# FPGA.net
KiCad netlist of a schematic drawn in Altium Designer
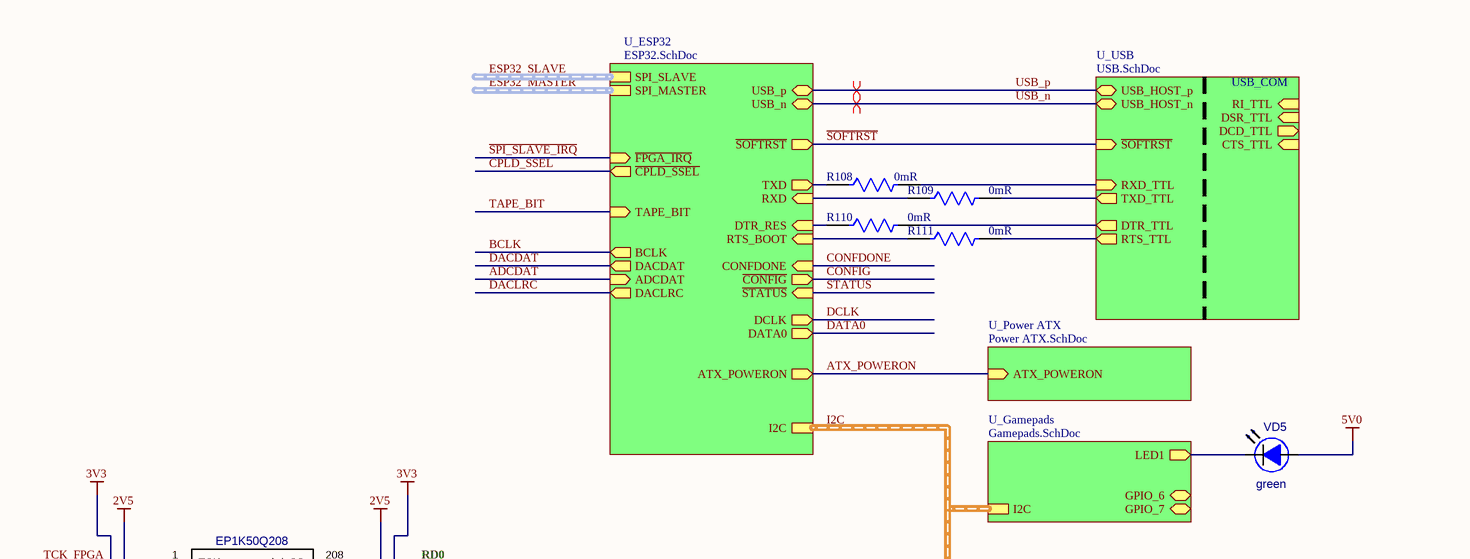
[diagram p0: FPGA.SchDoc, top]
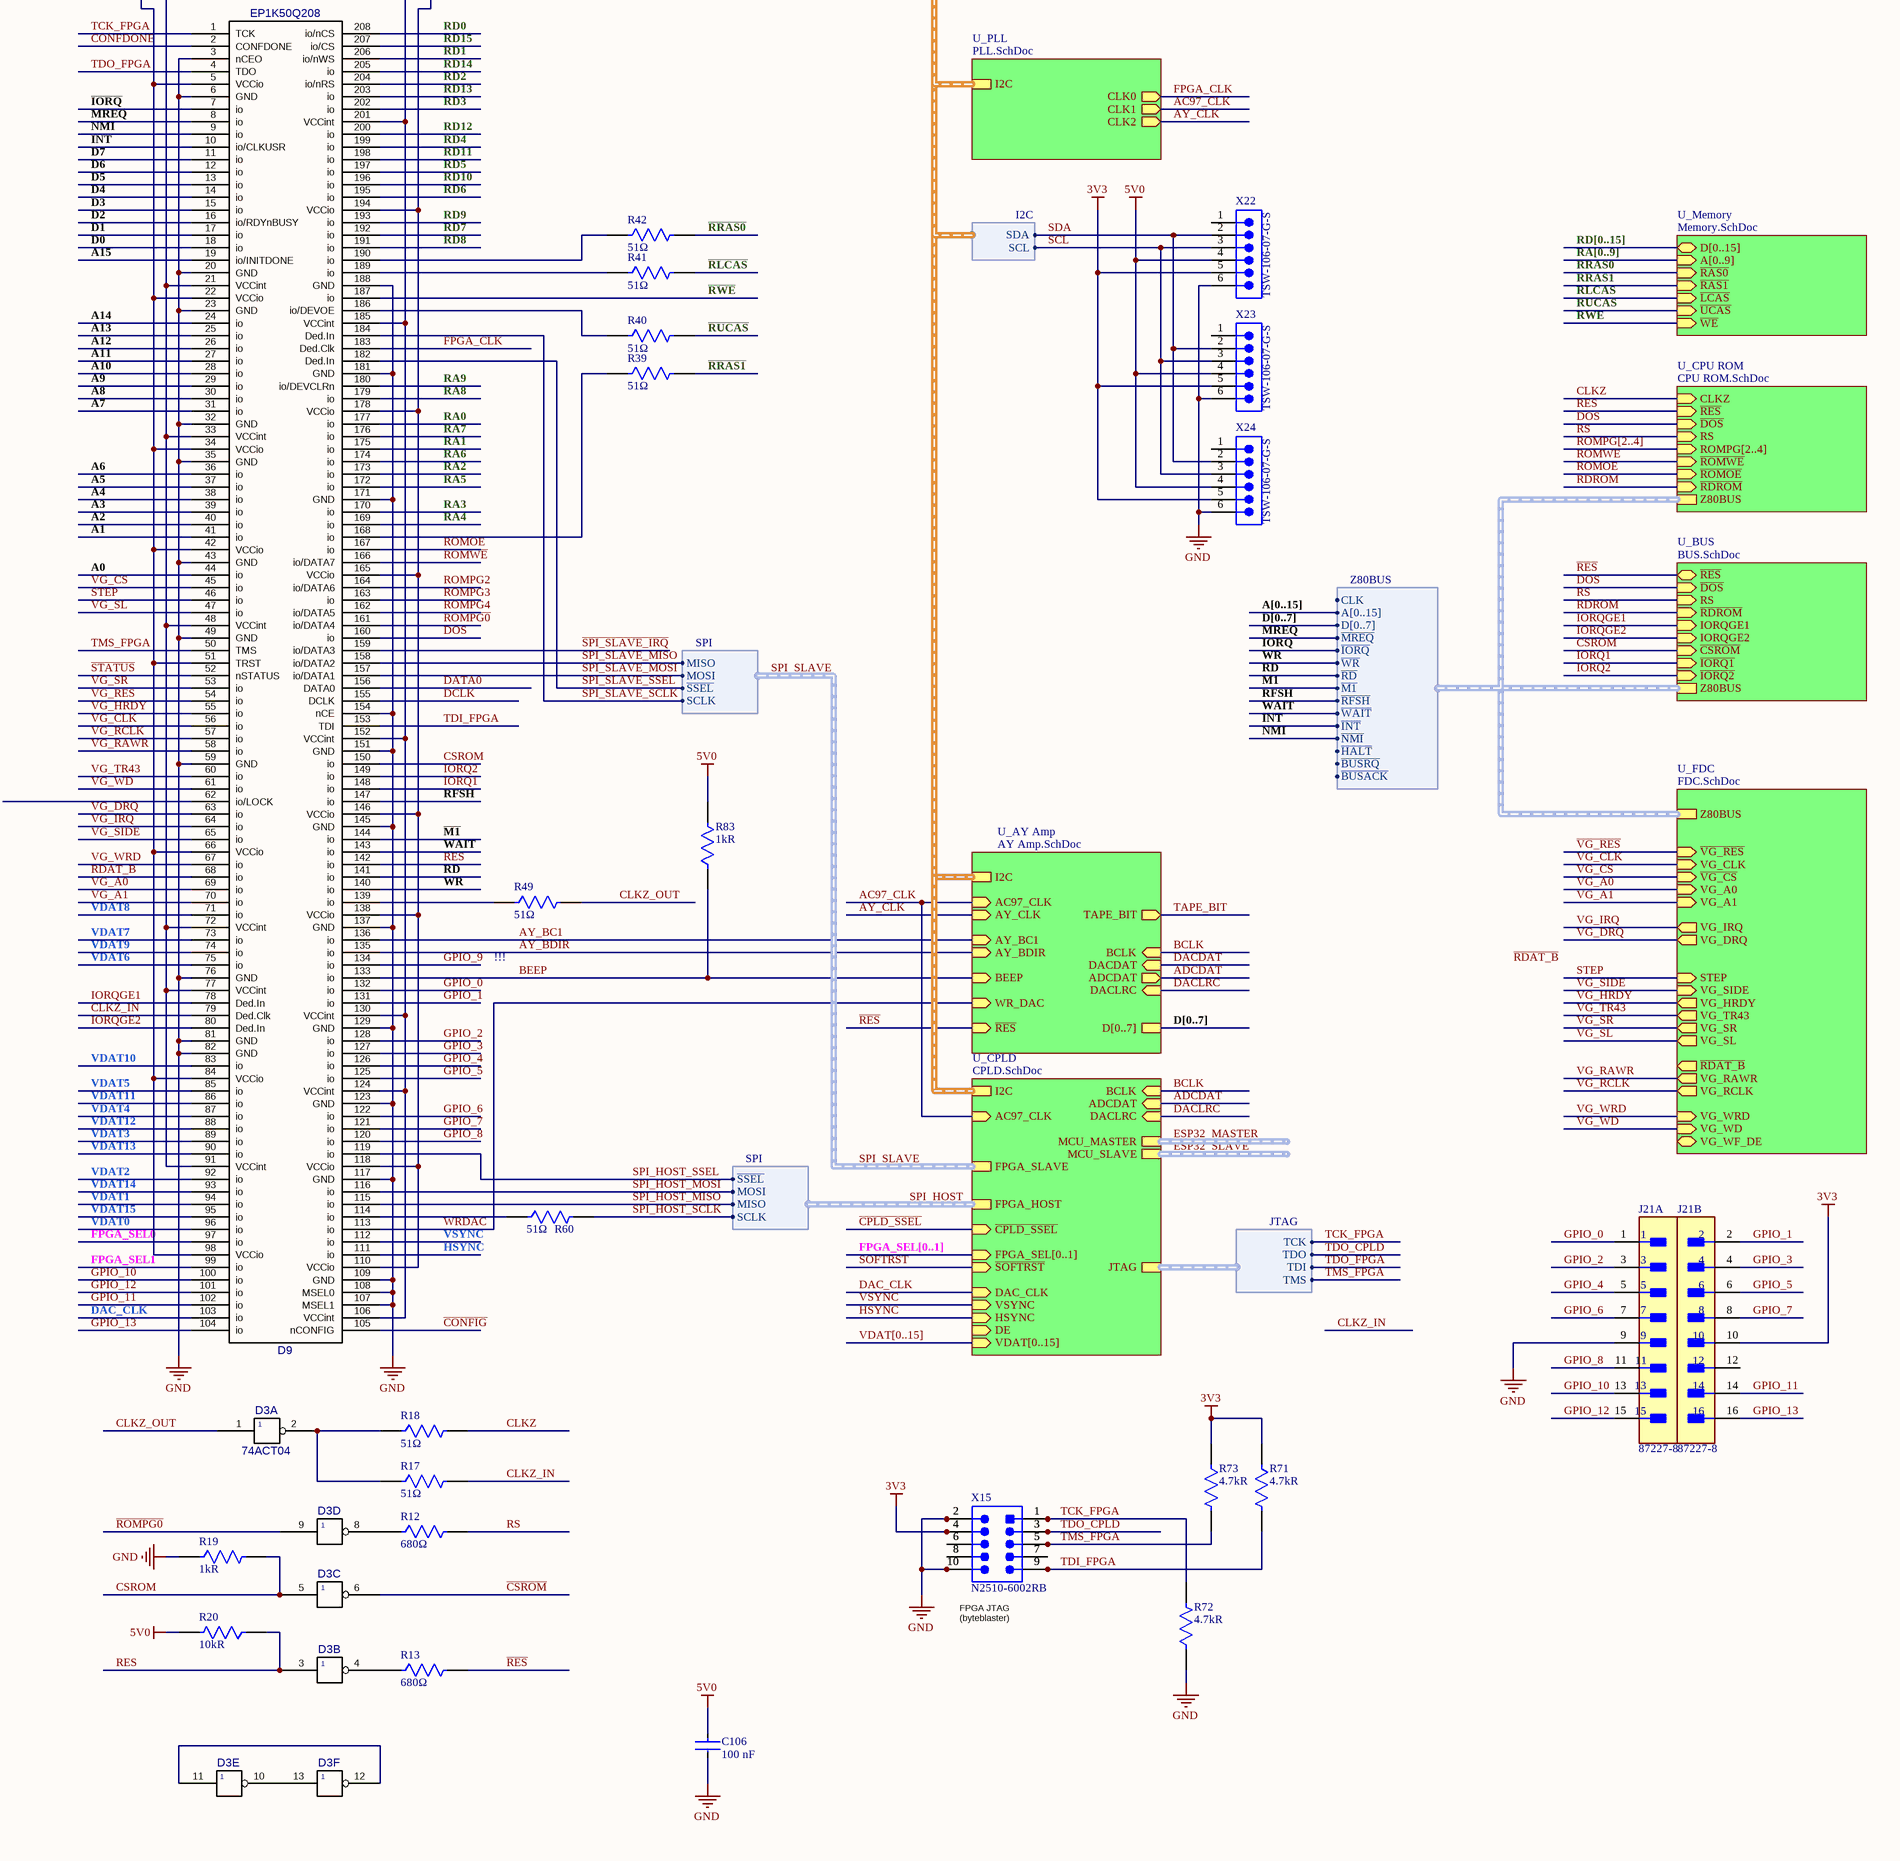
[diagram p1: FPGA.SchDoc, bottom]

(export (version "E")
  (design (tool "Eeschema 10.0.6"))
  (components
    (comp (ref "C106")
      (value "CC0805KRX7R9BB104")
      (footprint "FP-CC0805-0_85-IPC_A")
      (description "CAP CER 0.1UF 50V X7R 0805")
      (fields (field (name "CAPACITANCE") "100 nF") (field (name "MANUFACTURER") "Yageo"))
      (libsource (lib "SchLib") (part "CMP-2100-03606-3"))
    )
    (comp (ref "D3")
      (value "74ACT04")
      (footprint "SO14")
      (description "04")
      (libsource (lib "SchLib") (part "04"))
    )
    (comp (ref "D9")
      (value "EP1K50Q208")
      (footprint "PQFP208X5")
      (libsource (lib "SchLib") (part "EP1K50Q208"))
    )
    (comp (ref "J21")
      (value "87227-8")
      (footprint "FP-87227-8-MFG")
      (description "CONN HEADER VERT 16POS 2.54MM")
      (fields (field (name "MANUFACTURER") "TE Connectivity"))
      (libsource (lib "SchLib") (part "CMP-03369-000064-1"))
    )
    (comp (ref "R12")
      (value "680Ω")
      (footprint "FP-RT0805-IPC_A")
      (description "RES SMD 680 OHM 1% 1/8W 0805")
      (fields
        (field (name "MANUFACTURER") "Yageo")
        (field (name "MANUFACTURER PART NUMBER") "RT0805FRE07680RL")
      )
      (libsource (lib "SchLib") (part "CMP-03412-000082-1"))
    )
    (comp (ref "R13")
      (value "680Ω")
      (footprint "FP-RT0805-IPC_A")
      (description "RES SMD 680 OHM 1% 1/8W 0805")
      (fields
        (field (name "MANUFACTURER") "Yageo")
        (field (name "MANUFACTURER PART NUMBER") "RT0805FRE07680RL")
      )
      (libsource (lib "SchLib") (part "CMP-03412-000082-1"))
    )
    (comp (ref "R17")
      (value "RR1220Q-510-D")
      (footprint "FP-RR1220-IPC_A")
      (description "51Ω ±0.5% 0.1W 1/10W Chip Resistor 0805 (2012 Metric) Thin Film")
      (fields (field (name "RESISTANCE") "51Ω") (field (name "MANUFACTURER") "Susumu"))
      (libsource (lib "SchLib") (part "CMP-2001-03561-2"))
    )
    (comp (ref "R18")
      (value "RR1220Q-510-D")
      (footprint "FP-RR1220-IPC_A")
      (description "51Ω ±0.5% 0.1W 1/10W Chip Resistor 0805 (2012 Metric) Thin Film")
      (fields (field (name "RESISTANCE") "51Ω") (field (name "MANUFACTURER") "Susumu"))
      (libsource (lib "SchLib") (part "CMP-2001-03561-2"))
    )
    (comp (ref "R19")
      (value "CRCW08051K00FKEAHP")
      (footprint "FP-CRCW0805-HPe3-IPC_A")
      (description "RES Thick Film, 1kΩ, 1%, 0.5W, 100ppm/°C, 0805")
      (fields (field (name "RESISTANCE") "1kR") (field (name "MANUFACTURER") "Vishay Dale"))
      (libsource (lib "SchLib") (part "CMP-02407-004529-1"))
    )
    (comp (ref "R20")
      (value "CR0805-JW-103ELF")
      (footprint "FP-CR0805-IPC_A")
      (description "Thick Film Chip Resistors 0805 10kΩ 0.125W 5% 200ppm/°C")
      (fields (field (name "RESISTANCE") "10kR") (field (name "MANUFACTURER") "Bourns"))
      (libsource (lib "SchLib") (part "CMP-07231-003873-1"))
    )
    (comp (ref "R39")
      (value "RR1220Q-510-D")
      (footprint "FP-RR1220-IPC_A")
      (description "51Ω ±0.5% 0.1W 1/10W Chip Resistor 0805 (2012 Metric) Thin Film")
      (fields (field (name "RESISTANCE") "51Ω") (field (name "MANUFACTURER") "Susumu"))
      (libsource (lib "SchLib") (part "CMP-2001-03561-2"))
    )
    (comp (ref "R40")
      (value "RR1220Q-510-D")
      (footprint "FP-RR1220-IPC_A")
      (description "51Ω ±0.5% 0.1W 1/10W Chip Resistor 0805 (2012 Metric) Thin Film")
      (fields (field (name "RESISTANCE") "51Ω") (field (name "MANUFACTURER") "Susumu"))
      (libsource (lib "SchLib") (part "CMP-2001-03561-2"))
    )
    (comp (ref "R41")
      (value "RR1220Q-510-D")
      (footprint "FP-RR1220-IPC_A")
      (description "51Ω ±0.5% 0.1W 1/10W Chip Resistor 0805 (2012 Metric) Thin Film")
      (fields (field (name "RESISTANCE") "51Ω") (field (name "MANUFACTURER") "Susumu"))
      (libsource (lib "SchLib") (part "CMP-2001-03561-2"))
    )
    (comp (ref "R42")
      (value "RR1220Q-510-D")
      (footprint "FP-RR1220-IPC_A")
      (description "51Ω ±0.5% 0.1W 1/10W Chip Resistor 0805 (2012 Metric) Thin Film")
      (fields (field (name "RESISTANCE") "51Ω") (field (name "MANUFACTURER") "Susumu"))
      (libsource (lib "SchLib") (part "CMP-2001-03561-2"))
    )
    (comp (ref "R49")
      (value "RR1220Q-510-D")
      (footprint "FP-RR1220-IPC_A")
      (description "51Ω ±0.5% 0.1W 1/10W Chip Resistor 0805 (2012 Metric) Thin Film")
      (fields (field (name "RESISTANCE") "51Ω") (field (name "MANUFACTURER") "Susumu"))
      (libsource (lib "SchLib") (part "CMP-2001-03561-2"))
    )
    (comp (ref "R60")
      (value "RR1220Q-510-D")
      (footprint "FP-RR1220-IPC_A")
      (description "51Ω ±0.5% 0.1W 1/10W Chip Resistor 0805 (2012 Metric) Thin Film")
      (fields (field (name "RESISTANCE") "51Ω") (field (name "MANUFACTURER") "Susumu"))
      (libsource (lib "SchLib") (part "CMP-2001-03561-2"))
    )
    (comp (ref "R71")
      (value "CR0805-JW-472ELF")
      (footprint "FP-CR0805-IPC_A")
      (description "Thick Film Chip Resistors 0805 4.7kΩ 0.125W 5% 200ppm/°C")
      (fields (field (name "RESISTANCE") "4.7kR") (field (name "MANUFACTURER") "Bourns"))
      (libsource (lib "SchLib") (part "CMP-07231-004713-1"))
    )
    (comp (ref "R72")
      (value "CR0805-JW-472ELF")
      (footprint "FP-CR0805-IPC_A")
      (description "Thick Film Chip Resistors 0805 4.7kΩ 0.125W 5% 200ppm/°C")
      (fields (field (name "RESISTANCE") "4.7kR") (field (name "MANUFACTURER") "Bourns"))
      (libsource (lib "SchLib") (part "CMP-07231-004713-1"))
    )
    (comp (ref "R73")
      (value "CR0805-JW-472ELF")
      (footprint "FP-CR0805-IPC_A")
      (description "Thick Film Chip Resistors 0805 4.7kΩ 0.125W 5% 200ppm/°C")
      (fields (field (name "RESISTANCE") "4.7kR") (field (name "MANUFACTURER") "Bourns"))
      (libsource (lib "SchLib") (part "CMP-07231-004713-1"))
    )
    (comp (ref "R83")
      (value "CRCW08051K00FKEAHP")
      (footprint "FP-CRCW0805-HPe3-IPC_A")
      (description "RES Thick Film, 1kΩ, 1%, 0.5W, 100ppm/°C, 0805")
      (fields (field (name "RESISTANCE") "1kR") (field (name "MANUFACTURER") "Vishay Dale"))
      (libsource (lib "SchLib") (part "CMP-02407-004529-1"))
    )
    (comp (ref "R108")
      (value "CR0805-J/-000ELF")
      (footprint "FP-CR0805-IPC_A")
      (description "Thick Film Chip Resistors 0805 0Ω 0.125W 5%")
      (fields (field (name "RESISTANCE") "0mR") (field (name "MANUFACTURER") "Bourns"))
      (libsource (lib "SchLib") (part "CMP-07231-004348-1"))
    )
    (comp (ref "R109")
      (value "CR0805-J/-000ELF")
      (footprint "FP-CR0805-IPC_A")
      (description "Thick Film Chip Resistors 0805 0Ω 0.125W 5%")
      (fields (field (name "RESISTANCE") "0mR") (field (name "MANUFACTURER") "Bourns"))
      (libsource (lib "SchLib") (part "CMP-07231-004348-1"))
    )
    (comp (ref "R110")
      (value "CR0805-J/-000ELF")
      (footprint "FP-CR0805-IPC_A")
      (description "Thick Film Chip Resistors 0805 0Ω 0.125W 5%")
      (fields (field (name "RESISTANCE") "0mR") (field (name "MANUFACTURER") "Bourns"))
      (libsource (lib "SchLib") (part "CMP-07231-004348-1"))
    )
    (comp (ref "R111")
      (value "CR0805-J/-000ELF")
      (footprint "FP-CR0805-IPC_A")
      (description "Thick Film Chip Resistors 0805 0Ω 0.125W 5%")
      (fields (field (name "RESISTANCE") "0mR") (field (name "MANUFACTURER") "Bourns"))
      (libsource (lib "SchLib") (part "CMP-07231-004348-1"))
    )
    (comp (ref "VD5")
      (value "green")
      (footprint "LED100_LED(Primary)")
      (description "Light Emitting Diode")
      (fields (field (name "Comment") "LED"))
      (libsource (lib "SchLib") (part "LED"))
    )
    (comp (ref "X15")
      (value "N2510-6002RB")
      (footprint "3M-N2510-6002-10_V")
      (fields (field (name "PARTNUMBER") "N2510") (field (name "MANUFACTURER") "3M"))
      (libsource (lib "SchLib") (part "CMP-2000-06794-1"))
    )
    (comp (ref "X22")
      (value "TSW-106-07-G-S")
      (footprint "SMTC-TSW-106-07-X-S")
      (description "0.025\" SQ Post Header, Through-hole, Vertical, -55 to 125 degC, 2.54 mm Pitch, 6-Pin, Male, RoHS")
      (fields (field (name "MANUFACTURER") "Samtec"))
      (libsource (lib "SchLib") (part "CMP-1024-00383-1"))
    )
    (comp (ref "X23")
      (value "TSW-106-07-G-S")
      (footprint "SMTC-TSW-106-07-X-S")
      (description "0.025\" SQ Post Header, Through-hole, Vertical, -55 to 125 degC, 2.54 mm Pitch, 6-Pin, Male, RoHS")
      (fields (field (name "MANUFACTURER") "Samtec"))
      (libsource (lib "SchLib") (part "CMP-1024-00383-1"))
    )
    (comp (ref "X24")
      (value "TSW-106-07-G-S")
      (footprint "SMTC-TSW-106-07-X-S")
      (description "0.025\" SQ Post Header, Through-hole, Vertical, -55 to 125 degC, 2.54 mm Pitch, 6-Pin, Male, RoHS")
      (fields (field (name "MANUFACTURER") "Samtec"))
      (libsource (lib "SchLib") (part "CMP-1024-00383-1"))
    )
  )
  (nets
    (net (code "7") (name "+5v") (class "Default")
      (node (ref "D3") (pin "14") (pinfunction "+5v_14") (pintype "power_in"))
    )
    (net (code "8") (name "/A0") (class "Default")
      (node (ref "D9") (pin "44") (pinfunction "io_44") (pintype "passive"))
    )
    (net (code "9") (name "/A1") (class "Default")
      (node (ref "D9") (pin "41") (pinfunction "io_41") (pintype "passive"))
    )
    (net (code "10") (name "/A2") (class "Default")
      (node (ref "D9") (pin "40") (pinfunction "io_40") (pintype "passive"))
    )
    (net (code "11") (name "/A3") (class "Default")
      (node (ref "D9") (pin "39") (pinfunction "io_39") (pintype "passive"))
    )
    (net (code "12") (name "/A4") (class "Default")
      (node (ref "D9") (pin "38") (pinfunction "io_38") (pintype "passive"))
    )
    (net (code "13") (name "/A5") (class "Default")
      (node (ref "D9") (pin "37") (pinfunction "io_37") (pintype "passive"))
    )
    (net (code "14") (name "/A6") (class "Default")
      (node (ref "D9") (pin "36") (pinfunction "io_36") (pintype "passive"))
    )
    (net (code "15") (name "/A7") (class "Default")
      (node (ref "D9") (pin "31") (pinfunction "io_31") (pintype "passive"))
    )
    (net (code "16") (name "/A8") (class "Default")
      (node (ref "D9") (pin "30") (pinfunction "io_30") (pintype "passive"))
    )
    (net (code "17") (name "/A9") (class "Default")
      (node (ref "D9") (pin "29") (pinfunction "io_29") (pintype "passive"))
    )
    (net (code "18") (name "/A10") (class "Default")
      (node (ref "D9") (pin "28") (pinfunction "io_28") (pintype "passive"))
    )
    (net (code "19") (name "/A11") (class "Default")
      (node (ref "D9") (pin "27") (pinfunction "io_27") (pintype "passive"))
    )
    (net (code "20") (name "/A12") (class "Default")
      (node (ref "D9") (pin "26") (pinfunction "io_26") (pintype "passive"))
    )
    (net (code "21") (name "/A13") (class "Default")
      (node (ref "D9") (pin "25") (pinfunction "io_25") (pintype "passive"))
    )
    (net (code "22") (name "/A14") (class "Default")
      (node (ref "D9") (pin "24") (pinfunction "io_24") (pintype "passive"))
    )
    (net (code "23") (name "/A15") (class "Default")
      (node (ref "D9") (pin "19") (pinfunction "io/INITDONE_19") (pintype "passive"))
    )
    (net (code "27") (name "/AY_BC1") (class "Default")
      (node (ref "D9") (pin "136") (pinfunction "io_136") (pintype "passive"))
    )
    (net (code "28") (name "/AY_BDIR") (class "Default")
      (node (ref "D9") (pin "135") (pinfunction "io_135") (pintype "passive"))
    )
    (net (code "32") (name "/BEEP") (class "Default")
      (node (ref "D9") (pin "133") (pinfunction "io_133") (pintype "passive"))
      (node (ref "R83") (pin "1") (pinfunction "1_1") (pintype "passive"))
    )
    (net (code "33") (name "/CLKZ") (class "Default")
      (node (ref "R18") (pin "2") (pinfunction "2_2") (pintype "passive"))
    )
    (net (code "34") (name "/CLKZ_IN") (class "Default")
      (node (ref "D9") (pin "79") (pinfunction "Ded.Clk_79") (pintype "passive"))
      (node (ref "R17") (pin "2") (pinfunction "2_2") (pintype "passive"))
    )
    (net (code "35") (name "/CLKZ_OUT") (class "Default")
      (node (ref "D3") (pin "1") (pintype "passive"))
      (node (ref "R49") (pin "2") (pinfunction "2_2") (pintype "passive"))
    )
    (net (code "36") (name "/CONFDONE") (class "Default")
      (node (ref "D9") (pin "2") (pinfunction "CONFDONE_2") (pintype "passive"))
    )
    (net (code "37") (name "/CSROM") (class "Default")
      (node (ref "D3") (pin "5") (pintype "passive"))
      (node (ref "D9") (pin "150") (pinfunction "io_150") (pintype "passive"))
      (node (ref "R19") (pin "2") (pinfunction "2_2") (pintype "passive"))
    )
    (net (code "39") (name "/D0") (class "Default")
      (node (ref "D9") (pin "18") (pinfunction "io_18") (pintype "passive"))
    )
    (net (code "40") (name "/D1") (class "Default")
      (node (ref "D9") (pin "17") (pinfunction "io_17") (pintype "passive"))
    )
    (net (code "41") (name "/D2") (class "Default")
      (node (ref "D9") (pin "16") (pinfunction "io/RDYnBUSY_16") (pintype "passive"))
    )
    (net (code "42") (name "/D3") (class "Default")
      (node (ref "D9") (pin "15") (pinfunction "io_15") (pintype "passive"))
    )
    (net (code "43") (name "/D4") (class "Default")
      (node (ref "D9") (pin "14") (pinfunction "io_14") (pintype "passive"))
    )
    (net (code "44") (name "/D5") (class "Default")
      (node (ref "D9") (pin "13") (pinfunction "io_13") (pintype "passive"))
    )
    (net (code "45") (name "/D6") (class "Default")
      (node (ref "D9") (pin "12") (pinfunction "io_12") (pintype "passive"))
    )
    (net (code "46") (name "/D7") (class "Default")
      (node (ref "D9") (pin "11") (pinfunction "io_11") (pintype "passive"))
    )
    (net (code "49") (name "/DAC_CLK") (class "Default")
      (node (ref "D9") (pin "103") (pinfunction "io_103") (pintype "passive"))
    )
    (net (code "50") (name "/DATA0") (class "Default")
      (node (ref "D9") (pin "156") (pinfunction "DATA0_156") (pintype "passive"))
    )
    (net (code "52") (name "/DCLK") (class "Default")
      (node (ref "D9") (pin "155") (pinfunction "DCLK_155") (pintype "passive"))
    )
    (net (code "55") (name "/DTR_RES") (class "Default")
      (node (ref "R110") (pin "1") (pinfunction "1_1") (pintype "passive"))
    )
    (net (code "56") (name "/DTR_TTL") (class "Default")
      (node (ref "R110") (pin "2") (pinfunction "2_2") (pintype "passive"))
    )
    (net (code "58") (name "/FPGA_CLK") (class "Default")
      (node (ref "D9") (pin "183") (pinfunction "Ded.Clk_183") (pintype "passive"))
    )
    (net (code "59") (name "/FPGA_SEL0") (class "Default")
      (node (ref "D9") (pin "97") (pinfunction "io_97") (pintype "passive"))
    )
    (net (code "60") (name "/FPGA_SEL1") (class "Default")
      (node (ref "D9") (pin "99") (pinfunction "io_99") (pintype "passive"))
    )
    (net (code "62") (name "/GPIO_0") (class "Default")
      (node (ref "D9") (pin "132") (pinfunction "io_132") (pintype "passive"))
      (node (ref "J21") (pin "1") (pinfunction "1_1") (pintype "passive"))
    )
    (net (code "63") (name "/GPIO_1") (class "Default")
      (node (ref "D9") (pin "131") (pinfunction "io_131") (pintype "passive"))
      (node (ref "J21") (pin "2") (pinfunction "2_2") (pintype "passive"))
    )
    (net (code "64") (name "/GPIO_2") (class "Default")
      (node (ref "D9") (pin "128") (pinfunction "io_128") (pintype "passive"))
      (node (ref "J21") (pin "3") (pinfunction "3_3") (pintype "passive"))
    )
    (net (code "65") (name "/GPIO_3") (class "Default")
      (node (ref "D9") (pin "127") (pinfunction "io_127") (pintype "passive"))
      (node (ref "J21") (pin "4") (pinfunction "4_4") (pintype "passive"))
    )
    (net (code "66") (name "/GPIO_4") (class "Default")
      (node (ref "D9") (pin "126") (pinfunction "io_126") (pintype "passive"))
      (node (ref "J21") (pin "5") (pinfunction "5_5") (pintype "passive"))
    )
    (net (code "67") (name "/GPIO_5") (class "Default")
      (node (ref "D9") (pin "125") (pinfunction "io_125") (pintype "passive"))
      (node (ref "J21") (pin "6") (pinfunction "6_6") (pintype "passive"))
    )
    (net (code "68") (name "/GPIO_6") (class "Default")
      (node (ref "D9") (pin "122") (pinfunction "io_122") (pintype "passive"))
      (node (ref "J21") (pin "7") (pinfunction "7_7") (pintype "passive"))
    )
    (net (code "70") (name "/GPIO_7") (class "Default")
      (node (ref "D9") (pin "121") (pinfunction "io_121") (pintype "passive"))
      (node (ref "J21") (pin "8") (pinfunction "8_8") (pintype "passive"))
    )
    (net (code "72") (name "/GPIO_8") (class "Default")
      (node (ref "D9") (pin "120") (pinfunction "io_120") (pintype "passive"))
      (node (ref "J21") (pin "11") (pinfunction "11_11") (pintype "passive"))
    )
    (net (code "73") (name "/GPIO_9") (class "Default")
      (node (ref "D9") (pin "134") (pinfunction "io_134") (pintype "passive"))
    )
    (net (code "74") (name "/GPIO_10") (class "Default")
      (node (ref "D9") (pin "100") (pinfunction "io_100") (pintype "passive"))
      (node (ref "J21") (pin "13") (pinfunction "13_13") (pintype "passive"))
    )
    (net (code "75") (name "/GPIO_11") (class "Default")
      (node (ref "D9") (pin "102") (pinfunction "io_102") (pintype "passive"))
      (node (ref "J21") (pin "14") (pinfunction "14_14") (pintype "passive"))
    )
    (net (code "76") (name "/GPIO_12") (class "Default")
      (node (ref "D9") (pin "101") (pinfunction "io_101") (pintype "passive"))
      (node (ref "J21") (pin "15") (pinfunction "15_15") (pintype "passive"))
    )
    (net (code "77") (name "/GPIO_13") (class "Default")
      (node (ref "D9") (pin "104") (pinfunction "io_104") (pintype "passive"))
      (node (ref "J21") (pin "16") (pinfunction "16_16") (pintype "passive"))
    )
    (net (code "78") (name "/HSYNC") (class "Default")
      (node (ref "D9") (pin "111") (pinfunction "io_111") (pintype "passive"))
    )
    (net (code "80") (name "/IORQGE1") (class "Default")
      (node (ref "D9") (pin "78") (pinfunction "Ded.In_78") (pintype "passive"))
    )
    (net (code "81") (name "/IORQGE2") (class "Default")
      (node (ref "D9") (pin "80") (pinfunction "Ded.In_80") (pintype "passive"))
    )
    (net (code "82") (name "/LED1") (class "Default")
      (node (ref "VD5") (pin "K") (pinfunction "K_K") (pintype "passive"))
    )
    (net (code "83") (name "/RA0") (class "Default")
      (node (ref "D9") (pin "177") (pinfunction "io_177") (pintype "passive"))
    )
    (net (code "84") (name "/RA1") (class "Default")
      (node (ref "D9") (pin "175") (pinfunction "io_175") (pintype "passive"))
    )
    (net (code "85") (name "/RA2") (class "Default")
      (node (ref "D9") (pin "173") (pinfunction "io_173") (pintype "passive"))
    )
    (net (code "86") (name "/RA3") (class "Default")
      (node (ref "D9") (pin "170") (pinfunction "io_170") (pintype "passive"))
    )
    (net (code "87") (name "/RA4") (class "Default")
      (node (ref "D9") (pin "169") (pinfunction "io_169") (pintype "passive"))
    )
    (net (code "88") (name "/RA5") (class "Default")
      (node (ref "D9") (pin "172") (pinfunction "io_172") (pintype "passive"))
    )
    (net (code "89") (name "/RA6") (class "Default")
      (node (ref "D9") (pin "174") (pinfunction "io_174") (pintype "passive"))
    )
    (net (code "90") (name "/RA7") (class "Default")
      (node (ref "D9") (pin "176") (pinfunction "io_176") (pintype "passive"))
    )
    (net (code "91") (name "/RA8") (class "Default")
      (node (ref "D9") (pin "179") (pinfunction "io_179") (pintype "passive"))
    )
    (net (code "92") (name "/RA9") (class "Default")
      (node (ref "D9") (pin "180") (pinfunction "io/DEVCLRn_180") (pintype "passive"))
    )
    (net (code "94") (name "/RD0") (class "Default")
      (node (ref "D9") (pin "208") (pinfunction "io/nCS_208") (pintype "passive"))
    )
    (net (code "95") (name "/RD1") (class "Default")
      (node (ref "D9") (pin "206") (pinfunction "io/nWS_206") (pintype "passive"))
    )
    (net (code "96") (name "/RD2") (class "Default")
      (node (ref "D9") (pin "204") (pinfunction "io/nRS_204") (pintype "passive"))
    )
    (net (code "97") (name "/RD3") (class "Default")
      (node (ref "D9") (pin "202") (pinfunction "io_202") (pintype "passive"))
    )
    (net (code "98") (name "/RD4") (class "Default")
      (node (ref "D9") (pin "199") (pinfunction "io_199") (pintype "passive"))
    )
    (net (code "99") (name "/RD5") (class "Default")
      (node (ref "D9") (pin "197") (pinfunction "io_197") (pintype "passive"))
    )
    (net (code "100") (name "/RD6") (class "Default")
      (node (ref "D9") (pin "195") (pinfunction "io_195") (pintype "passive"))
    )
    (net (code "101") (name "/RD7") (class "Default")
      (node (ref "D9") (pin "192") (pinfunction "io_192") (pintype "passive"))
    )
    (net (code "102") (name "/RD8") (class "Default")
      (node (ref "D9") (pin "191") (pinfunction "io_191") (pintype "passive"))
    )
    (net (code "103") (name "/RD9") (class "Default")
      (node (ref "D9") (pin "193") (pinfunction "io_193") (pintype "passive"))
    )
    (net (code "104") (name "/RD10") (class "Default")
      (node (ref "D9") (pin "196") (pinfunction "io_196") (pintype "passive"))
    )
    (net (code "105") (name "/RD11") (class "Default")
      (node (ref "D9") (pin "198") (pinfunction "io_198") (pintype "passive"))
    )
    (net (code "106") (name "/RD12") (class "Default")
      (node (ref "D9") (pin "200") (pinfunction "io_200") (pintype "passive"))
    )
    (net (code "107") (name "/RD13") (class "Default")
      (node (ref "D9") (pin "203") (pinfunction "io_203") (pintype "passive"))
    )
    (net (code "108") (name "/RD14") (class "Default")
      (node (ref "D9") (pin "205") (pinfunction "io_205") (pintype "passive"))
    )
    (net (code "109") (name "/RD15") (class "Default")
      (node (ref "D9") (pin "207") (pinfunction "io/CS_207") (pintype "passive"))
    )
    (net (code "111") (name "/RES") (class "Default")
      (node (ref "D3") (pin "3") (pintype "passive"))
      (node (ref "D9") (pin "142") (pinfunction "io_142") (pintype "passive"))
      (node (ref "R20") (pin "1") (pinfunction "1_1") (pintype "passive"))
    )
    (net (code "113") (name "/ROMPG2") (class "Default")
      (node (ref "D9") (pin "164") (pinfunction "io/DATA6_164") (pintype "passive"))
    )
    (net (code "114") (name "/ROMPG3") (class "Default")
      (node (ref "D9") (pin "163") (pinfunction "io_163") (pintype "passive"))
    )
    (net (code "115") (name "/ROMPG4") (class "Default")
      (node (ref "D9") (pin "162") (pinfunction "io/DATA5_162") (pintype "passive"))
    )
    (net (code "117") (name "/RS") (class "Default")
      (node (ref "R12") (pin "2") (pinfunction "2_2") (pintype "passive"))
    )
    (net (code "118") (name "/RTS_BOOT") (class "Default")
      (node (ref "R111") (pin "1") (pinfunction "1_1") (pintype "passive"))
    )
    (net (code "119") (name "/RTS_TTL") (class "Default")
      (node (ref "R111") (pin "2") (pinfunction "2_2") (pintype "passive"))
    )
    (net (code "120") (name "/RXD") (class "Default")
      (node (ref "R109") (pin "1") (pinfunction "1_1") (pintype "passive"))
    )
    (net (code "121") (name "/RXD_TTL") (class "Default")
      (node (ref "R108") (pin "2") (pinfunction "2_2") (pintype "passive"))
    )
    (net (code "122") (name "/SCL") (class "Default")
      (node (ref "X22") (pin "3") (pinfunction "3_3") (pintype "passive"))
      (node (ref "X23") (pin "3") (pinfunction "3_3") (pintype "passive"))
      (node (ref "X24") (pin "3") (pinfunction "3_3") (pintype "passive"))
    )
    (net (code "123") (name "/SDA") (class "Default")
      (node (ref "X22") (pin "2") (pinfunction "2_2") (pintype "passive"))
      (node (ref "X23") (pin "2") (pinfunction "2_2") (pintype "passive"))
      (node (ref "X24") (pin "2") (pinfunction "2_2") (pintype "passive"))
    )
    (net (code "124") (name "/SPI_HOST_MISO") (class "Default")
      (node (ref "D9") (pin "115") (pinfunction "io_115") (pintype "passive"))
    )
    (net (code "125") (name "/SPI_HOST_MOSI") (class "Default")
      (node (ref "D9") (pin "116") (pinfunction "io_116") (pintype "passive"))
    )
    (net (code "126") (name "/SPI_HOST_SCLK") (class "Default")
      (node (ref "R60") (pin "2") (pinfunction "2_2") (pintype "passive"))
    )
    (net (code "127") (name "/SPI_HOST_SSEL") (class "Default")
      (node (ref "D9") (pin "119") (pinfunction "io_119") (pintype "passive"))
    )
    (net (code "129") (name "/SPI_SLAVE_MISO") (class "Default")
      (node (ref "D9") (pin "158") (pinfunction "io/DATA2_158") (pintype "passive"))
    )
    (net (code "130") (name "/SPI_SLAVE_MOSI") (class "Default")
      (node (ref "D9") (pin "157") (pinfunction "io/DATA1_157") (pintype "passive"))
    )
    (net (code "131") (name "/SPI_SLAVE_SCLK") (class "Default")
      (node (ref "D9") (pin "184") (pinfunction "Ded.In_184") (pintype "passive"))
    )
    (net (code "133") (name "/STEP") (class "Default")
      (node (ref "D9") (pin "46") (pinfunction "io_46") (pintype "passive"))
    )
    (net (code "135") (name "/TCK_FPGA") (class "Default")
      (node (ref "D9") (pin "1") (pinfunction "TCK_1") (pintype "passive"))
      (node (ref "R72") (pin "2") (pinfunction "2_2") (pintype "passive"))
      (node (ref "X15") (pin "1") (pinfunction "1_1") (pintype "passive"))
    )
    (net (code "136") (name "/TDI_FPGA") (class "Default")
      (node (ref "D9") (pin "153") (pinfunction "TDI_153") (pintype "passive"))
      (node (ref "R71") (pin "2") (pinfunction "2_2") (pintype "passive"))
      (node (ref "X15") (pin "9") (pinfunction "9_9") (pintype "passive"))
    )
    (net (code "137") (name "/TDO_CPLD") (class "Default")
      (node (ref "X15") (pin "3") (pinfunction "3_3") (pintype "passive"))
    )
    (net (code "138") (name "/TDO_FPGA") (class "Default")
      (node (ref "D9") (pin "4") (pinfunction "TDO_4") (pintype "passive"))
    )
    (net (code "139") (name "/TMS_FPGA") (class "Default")
      (node (ref "D9") (pin "50") (pinfunction "TMS_50") (pintype "passive"))
      (node (ref "R73") (pin "2") (pinfunction "2_2") (pintype "passive"))
      (node (ref "X15") (pin "5") (pinfunction "5_5") (pintype "passive"))
    )
    (net (code "140") (name "/TXD") (class "Default")
      (node (ref "R108") (pin "1") (pinfunction "1_1") (pintype "passive"))
    )
    (net (code "141") (name "/TXD_TTL") (class "Default")
      (node (ref "R109") (pin "2") (pinfunction "2_2") (pintype "passive"))
    )
    (net (code "144") (name "/VDAT0") (class "Default")
      (node (ref "D9") (pin "96") (pinfunction "io_96") (pintype "passive"))
    )
    (net (code "145") (name "/VDAT1") (class "Default")
      (node (ref "D9") (pin "94") (pinfunction "io_94") (pintype "passive"))
    )
    (net (code "146") (name "/VDAT2") (class "Default")
      (node (ref "D9") (pin "92") (pinfunction "io_92") (pintype "passive"))
    )
    (net (code "147") (name "/VDAT3") (class "Default")
      (node (ref "D9") (pin "89") (pinfunction "io_89") (pintype "passive"))
    )
    (net (code "148") (name "/VDAT4") (class "Default")
      (node (ref "D9") (pin "87") (pinfunction "io_87") (pintype "passive"))
    )
    (net (code "149") (name "/VDAT5") (class "Default")
      (node (ref "D9") (pin "85") (pinfunction "io_85") (pintype "passive"))
    )
    (net (code "150") (name "/VDAT6") (class "Default")
      (node (ref "D9") (pin "75") (pinfunction "io_75") (pintype "passive"))
    )
    (net (code "151") (name "/VDAT7") (class "Default")
      (node (ref "D9") (pin "73") (pinfunction "io_73") (pintype "passive"))
    )
    (net (code "152") (name "/VDAT8") (class "Default")
      (node (ref "D9") (pin "71") (pinfunction "io_71") (pintype "passive"))
    )
    (net (code "153") (name "/VDAT9") (class "Default")
      (node (ref "D9") (pin "74") (pinfunction "io_74") (pintype "passive"))
    )
    (net (code "154") (name "/VDAT10") (class "Default")
      (node (ref "D9") (pin "83") (pinfunction "io_83") (pintype "passive"))
    )
    (net (code "155") (name "/VDAT11") (class "Default")
      (node (ref "D9") (pin "86") (pinfunction "io_86") (pintype "passive"))
    )
    (net (code "156") (name "/VDAT12") (class "Default")
      (node (ref "D9") (pin "88") (pinfunction "io_88") (pintype "passive"))
    )
    (net (code "157") (name "/VDAT13") (class "Default")
      (node (ref "D9") (pin "90") (pinfunction "io_90") (pintype "passive"))
    )
    (net (code "158") (name "/VDAT14") (class "Default")
      (node (ref "D9") (pin "93") (pinfunction "io_93") (pintype "passive"))
    )
    (net (code "159") (name "/VDAT15") (class "Default")
      (node (ref "D9") (pin "95") (pinfunction "io_95") (pintype "passive"))
    )
    (net (code "161") (name "/VG_A0") (class "Default")
      (node (ref "D9") (pin "69") (pinfunction "io_69") (pintype "passive"))
    )
    (net (code "162") (name "/VG_A1") (class "Default")
      (node (ref "D9") (pin "70") (pinfunction "io_70") (pintype "passive"))
    )
    (net (code "163") (name "/VG_CLK") (class "Default")
      (node (ref "D9") (pin "56") (pinfunction "io_56") (pintype "passive"))
    )
    (net (code "164") (name "/VG_DRQ") (class "Default")
      (node (ref "D9") (pin "63") (pinfunction "io_63") (pintype "passive"))
    )
    (net (code "165") (name "/VG_HRDY") (class "Default")
      (node (ref "D9") (pin "55") (pinfunction "io_55") (pintype "passive"))
    )
    (net (code "166") (name "/VG_IRQ") (class "Default")
      (node (ref "D9") (pin "64") (pinfunction "io_64") (pintype "passive"))
    )
    (net (code "167") (name "/VG_RAWR") (class "Default")
      (node (ref "D9") (pin "58") (pinfunction "io_58") (pintype "passive"))
    )
    (net (code "168") (name "/VG_RCLK") (class "Default")
      (node (ref "D9") (pin "57") (pinfunction "io_57") (pintype "passive"))
    )
    (net (code "169") (name "/VG_SIDE") (class "Default")
      (node (ref "D9") (pin "65") (pinfunction "io_65") (pintype "passive"))
    )
    (net (code "170") (name "/VG_SL") (class "Default")
      (node (ref "D9") (pin "47") (pinfunction "io_47") (pintype "passive"))
    )
    (net (code "171") (name "/VG_SR") (class "Default")
      (node (ref "D9") (pin "53") (pinfunction "io_53") (pintype "passive"))
    )
    (net (code "172") (name "/VG_TR43") (class "Default")
      (node (ref "D9") (pin "60") (pinfunction "io_60") (pintype "passive"))
    )
    (net (code "173") (name "/VG_WD") (class "Default")
      (node (ref "D9") (pin "61") (pinfunction "io_61") (pintype "passive"))
    )
    (net (code "175") (name "/VG_WRD") (class "Default")
      (node (ref "D9") (pin "67") (pinfunction "io_67") (pintype "passive"))
    )
    (net (code "176") (name "/VSYNC") (class "Default")
      (node (ref "D9") (pin "112") (pinfunction "io_112") (pintype "passive"))
    )
    (net (code "177") (name "/WRDAC") (class "Default")
      (node (ref "D9") (pin "113") (pinfunction "io_113") (pintype "passive"))
    )
    (net (code "183") (name "/~{CONFIG}") (class "Default")
      (node (ref "D9") (pin "105") (pinfunction "nCONFIG_105") (pintype "passive"))
    )
    (net (code "185") (name "/~{CSROM}") (class "Default") (node (ref "D3") (pin "6") (pintype "passive")))
    (net (code "186") (name "/~{DOS}") (class "Default")
      (node (ref "D9") (pin "160") (pinfunction "io_160") (pintype "passive"))
    )
    (net (code "187") (name "/~{INT}") (class "Default")
      (node (ref "D9") (pin "10") (pinfunction "io/CLKUSR_10") (pintype "passive"))
    )
    (net (code "188") (name "/~{IORQ1}") (class "Default")
      (node (ref "D9") (pin "148") (pinfunction "io_148") (pintype "passive"))
    )
    (net (code "189") (name "/~{IORQ2}") (class "Default")
      (node (ref "D9") (pin "149") (pinfunction "io_149") (pintype "passive"))
    )
    (net (code "190") (name "/~{IORQ}") (class "Default")
      (node (ref "D9") (pin "7") (pinfunction "io_7") (pintype "passive"))
    )
    (net (code "191") (name "/~{M1}") (class "Default")
      (node (ref "D9") (pin "144") (pinfunction "io_144") (pintype "passive"))
    )
    (net (code "192") (name "/~{MREQ}") (class "Default")
      (node (ref "D9") (pin "8") (pinfunction "io_8") (pintype "passive"))
    )
    (net (code "193") (name "/~{NMI}") (class "Default")
      (node (ref "D9") (pin "9") (pinfunction "io_9") (pintype "passive"))
    )
    (net (code "194") (name "/~{RDAT_B}") (class "Default")
      (node (ref "D9") (pin "68") (pinfunction "io_68") (pintype "passive"))
    )
    (net (code "197") (name "/~{RD}") (class "Default")
      (node (ref "D9") (pin "141") (pinfunction "io_141") (pintype "passive"))
    )
    (net (code "198") (name "/~{RES}") (class "Default")
      (node (ref "R13") (pin "2") (pinfunction "2_2") (pintype "passive"))
    )
    (net (code "199") (name "/~{RFSH}") (class "Default")
      (node (ref "D9") (pin "147") (pinfunction "io_147") (pintype "passive"))
    )
    (net (code "200") (name "/~{RLCAS}") (class "Default")
      (node (ref "R41") (pin "2") (pinfunction "2_2") (pintype "passive"))
    )
    (net (code "201") (name "/~{ROMOE}") (class "Default")
      (node (ref "D9") (pin "167") (pinfunction "io_167") (pintype "passive"))
    )
    (net (code "202") (name "/~{ROMPG0}") (class "Default")
      (node (ref "D3") (pin "9") (pintype "passive"))
      (node (ref "D9") (pin "161") (pinfunction "io/DATA4_161") (pintype "passive"))
    )
    (net (code "203") (name "/~{ROMWE}") (class "Default")
      (node (ref "D9") (pin "166") (pinfunction "io/DATA7_166") (pintype "passive"))
    )
    (net (code "204") (name "/~{RRAS0}") (class "Default")
      (node (ref "R42") (pin "2") (pinfunction "2_2") (pintype "passive"))
    )
    (net (code "205") (name "/~{RRAS1}") (class "Default")
      (node (ref "R39") (pin "2") (pinfunction "2_2") (pintype "passive"))
    )
    (net (code "206") (name "/~{RUCAS}") (class "Default")
      (node (ref "R40") (pin "2") (pinfunction "2_2") (pintype "passive"))
    )
    (net (code "207") (name "/~{RWE}") (class "Default")
      (node (ref "D9") (pin "187") (pinfunction "io_187") (pintype "passive"))
    )
    (net (code "209") (name "/~{SPI_SLAVE_IRQ}") (class "Default")
      (node (ref "D9") (pin "159") (pinfunction "io/DATA3_159") (pintype "passive"))
    )
    (net (code "210") (name "/~{SPI_SLAVE_SSEL}") (class "Default")
      (node (ref "D9") (pin "182") (pinfunction "Ded.In_182") (pintype "passive"))
    )
    (net (code "211") (name "/~{STATUS}") (class "Default")
      (node (ref "D9") (pin "52") (pinfunction "nSTATUS_52") (pintype "passive"))
    )
    (net (code "212") (name "/~{VG_CS}") (class "Default")
      (node (ref "D9") (pin "45") (pinfunction "io_45") (pintype "passive"))
    )
    (net (code "213") (name "/~{VG_RES}") (class "Default")
      (node (ref "D9") (pin "54") (pinfunction "io_54") (pintype "passive"))
    )
    (net (code "214") (name "/~{WAIT}") (class "Default")
      (node (ref "D9") (pin "143") (pinfunction "io_143") (pintype "passive"))
    )
    (net (code "215") (name "/~{WR}") (class "Default")
      (node (ref "D9") (pin "140") (pinfunction "io_140") (pintype "passive"))
    )
    (net (code "216") (name "2V5") (class "Default")
      (node (ref "D9") (pin "106") (pinfunction "VCCint_106") (pintype "passive"))
      (node (ref "D9") (pin "124") (pinfunction "VCCint_124") (pintype "passive"))
      (node (ref "D9") (pin "130") (pinfunction "VCCint_130") (pintype "passive"))
      (node (ref "D9") (pin "152") (pinfunction "VCCint_152") (pintype "passive"))
      (node (ref "D9") (pin "185") (pinfunction "VCCint_185") (pintype "passive"))
      (node (ref "D9") (pin "201") (pinfunction "VCCint_201") (pintype "passive"))
      (node (ref "D9") (pin "21") (pinfunction "VCCint_21") (pintype "passive"))
      (node (ref "D9") (pin "33") (pinfunction "VCCint_33") (pintype "passive"))
      (node (ref "D9") (pin "48") (pinfunction "VCCint_48") (pintype "passive"))
      (node (ref "D9") (pin "72") (pinfunction "VCCint_72") (pintype "passive"))
      (node (ref "D9") (pin "77") (pinfunction "VCCint_77") (pintype "passive"))
      (node (ref "D9") (pin "91") (pinfunction "VCCint_91") (pintype "passive"))
    )
    (net (code "217") (name "3V3") (class "Default")
      (node (ref "D9") (pin "110") (pinfunction "VCCio_110") (pintype "passive"))
      (node (ref "D9") (pin "118") (pinfunction "VCCio_118") (pintype "passive"))
      (node (ref "D9") (pin "138") (pinfunction "VCCio_138") (pintype "passive"))
      (node (ref "D9") (pin "146") (pinfunction "VCCio_146") (pintype "passive"))
      (node (ref "D9") (pin "165") (pinfunction "VCCio_165") (pintype "passive"))
      (node (ref "D9") (pin "178") (pinfunction "VCCio_178") (pintype "passive"))
      (node (ref "D9") (pin "194") (pinfunction "VCCio_194") (pintype "passive"))
      (node (ref "D9") (pin "22") (pinfunction "VCCio_22") (pintype "passive"))
      (node (ref "D9") (pin "34") (pinfunction "VCCio_34") (pintype "passive"))
      (node (ref "D9") (pin "42") (pinfunction "VCCio_42") (pintype "passive"))
      (node (ref "D9") (pin "5") (pinfunction "VCCio_5") (pintype "passive"))
      (node (ref "D9") (pin "51") (pinfunction "TRST_51") (pintype "passive"))
      (node (ref "D9") (pin "66") (pinfunction "VCCio_66") (pintype "passive"))
      (node (ref "D9") (pin "84") (pinfunction "VCCio_84") (pintype "passive"))
      (node (ref "D9") (pin "98") (pinfunction "VCCio_98") (pintype "passive"))
      (node (ref "J21") (pin "10") (pinfunction "10_10") (pintype "passive"))
      (node (ref "R71") (pin "1") (pinfunction "1_1") (pintype "passive"))
      (node (ref "R73") (pin "1") (pinfunction "1_1") (pintype "passive"))
      (node (ref "X15") (pin "4") (pinfunction "4_4") (pintype "passive"))
      (node (ref "X22") (pin "5") (pinfunction "5_5") (pintype "passive"))
      (node (ref "X23") (pin "5") (pinfunction "5_5") (pintype "passive"))
      (node (ref "X24") (pin "5") (pinfunction "5_5") (pintype "passive"))
    )
    (net (code "218") (name "5V0") (class "Default")
      (node (ref "C106") (pin "1") (pinfunction "1_1") (pintype "passive"))
      (node (ref "R20") (pin "2") (pinfunction "2_2") (pintype "passive"))
      (node (ref "R83") (pin "2") (pinfunction "2_2") (pintype "passive"))
      (node (ref "VD5") (pin "A") (pinfunction "A_A") (pintype "passive"))
      (node (ref "X22") (pin "4") (pinfunction "4_4") (pintype "passive"))
      (node (ref "X23") (pin "4") (pinfunction "4_4") (pintype "passive"))
      (node (ref "X24") (pin "4") (pinfunction "4_4") (pintype "passive"))
    )
    (net (code "219") (name "GND") (class "Default")
      (node (ref "C106") (pin "2") (pinfunction "2_2") (pintype "passive"))
      (node (ref "D3") (pin "7") (pinfunction "GND_7") (pintype "power_in"))
      (node (ref "D9") (pin "107") (pinfunction "MSEL1_107") (pintype "passive"))
      (node (ref "D9") (pin "108") (pinfunction "MSEL0_108") (pintype "passive"))
      (node (ref "D9") (pin "109") (pinfunction "GND_109") (pintype "passive"))
      (node (ref "D9") (pin "117") (pinfunction "GND_117") (pintype "passive"))
      (node (ref "D9") (pin "123") (pinfunction "GND_123") (pintype "passive"))
      (node (ref "D9") (pin "129") (pinfunction "GND_129") (pintype "passive"))
      (node (ref "D9") (pin "137") (pinfunction "GND_137") (pintype "passive"))
      (node (ref "D9") (pin "145") (pinfunction "GND_145") (pintype "passive"))
      (node (ref "D9") (pin "151") (pinfunction "GND_151") (pintype "passive"))
      (node (ref "D9") (pin "154") (pinfunction "nCE_154") (pintype "passive"))
      (node (ref "D9") (pin "171") (pinfunction "GND_171") (pintype "passive"))
      (node (ref "D9") (pin "181") (pinfunction "GND_181") (pintype "passive"))
      (node (ref "D9") (pin "188") (pinfunction "GND_188") (pintype "passive"))
      (node (ref "D9") (pin "20") (pinfunction "GND_20") (pintype "passive"))
      (node (ref "D9") (pin "23") (pinfunction "GND_23") (pintype "passive"))
      (node (ref "D9") (pin "3") (pinfunction "nCEO_3") (pintype "passive"))
      (node (ref "D9") (pin "32") (pinfunction "GND_32") (pintype "passive"))
      (node (ref "D9") (pin "35") (pinfunction "GND_35") (pintype "passive"))
      (node (ref "D9") (pin "43") (pinfunction "GND_43") (pintype "passive"))
      (node (ref "D9") (pin "49") (pinfunction "GND_49") (pintype "passive"))
      (node (ref "D9") (pin "59") (pinfunction "GND_59") (pintype "passive"))
      (node (ref "D9") (pin "6") (pinfunction "GND_6") (pintype "passive"))
      (node (ref "D9") (pin "76") (pinfunction "GND_76") (pintype "passive"))
      (node (ref "D9") (pin "81") (pinfunction "GND_81") (pintype "passive"))
      (node (ref "D9") (pin "82") (pinfunction "GND_82") (pintype "passive"))
      (node (ref "J21") (pin "9") (pinfunction "9_9") (pintype "passive"))
      (node (ref "R19") (pin "1") (pinfunction "1_1") (pintype "passive"))
      (node (ref "R72") (pin "1") (pinfunction "1_1") (pintype "passive"))
      (node (ref "X15") (pin "10") (pinfunction "10_10") (pintype "passive"))
      (node (ref "X15") (pin "2") (pinfunction "2_2") (pintype "passive"))
      (node (ref "X22") (pin "6") (pinfunction "6_6") (pintype "passive"))
      (node (ref "X23") (pin "6") (pinfunction "6_6") (pintype "passive"))
      (node (ref "X24") (pin "6") (pinfunction "6_6") (pintype "passive"))
    )
    (net (code "220") (name "Net-(D3-Pad2)") (class "Default")
      (node (ref "D3") (pin "2") (pintype "passive"))
      (node (ref "R17") (pin "1") (pinfunction "1_1") (pintype "passive"))
      (node (ref "R18") (pin "1") (pinfunction "1_1") (pintype "passive"))
    )
    (net (code "221") (name "Net-(D3-Pad4)") (class "Default")
      (node (ref "D3") (pin "4") (pintype "passive"))
      (node (ref "R13") (pin "1") (pinfunction "1_1") (pintype "passive"))
    )
    (net (code "222") (name "Net-(D3-Pad8)") (class "Default")
      (node (ref "D3") (pin "8") (pintype "passive"))
      (node (ref "R12") (pin "1") (pinfunction "1_1") (pintype "passive"))
    )
    (net (code "223") (name "Net-(D3-Pad10)") (class "Default")
      (node (ref "D3") (pin "10") (pintype "passive"))
      (node (ref "D3") (pin "13") (pintype "passive"))
    )
    (net (code "224") (name "Net-(D3-Pad11)") (class "Default")
      (node (ref "D3") (pin "11") (pintype "passive"))
      (node (ref "D3") (pin "12") (pintype "passive"))
    )
    (net (code "225") (name "Net-(D9-io-Pad114)") (class "Default")
      (node (ref "D9") (pin "114") (pinfunction "io_114") (pintype "passive"))
      (node (ref "R60") (pin "1") (pinfunction "1_1") (pintype "passive"))
    )
    (net (code "226") (name "Net-(D9-io-Pad139)") (class "Default")
      (node (ref "D9") (pin "139") (pinfunction "io_139") (pintype "passive"))
      (node (ref "R49") (pin "1") (pinfunction "1_1") (pintype "passive"))
    )
    (net (code "227") (name "Net-(D9-io-Pad168)") (class "Default")
      (node (ref "D9") (pin "168") (pinfunction "io_168") (pintype "passive"))
      (node (ref "R39") (pin "1") (pinfunction "1_1") (pintype "passive"))
    )
    (net (code "228") (name "Net-(D9-io-Pad189)") (class "Default")
      (node (ref "D9") (pin "189") (pinfunction "io_189") (pintype "passive"))
      (node (ref "R41") (pin "1") (pinfunction "1_1") (pintype "passive"))
    )
    (net (code "229") (name "Net-(D9-io-Pad190)") (class "Default")
      (node (ref "D9") (pin "190") (pinfunction "io_190") (pintype "passive"))
      (node (ref "R42") (pin "1") (pinfunction "1_1") (pintype "passive"))
    )
    (net (code "230") (name "Net-(D9-io{slash}DEVOE)") (class "Default")
      (node (ref "D9") (pin "186") (pinfunction "io/DEVOE_186") (pintype "passive"))
      (node (ref "R40") (pin "1") (pinfunction "1_1") (pintype "passive"))
    )
    (net (code "231") (name "Net-(X15-Pad6)") (class "Default")
      (node (ref "X15") (pin "6") (pinfunction "6_6") (pintype "passive"))
    )
    (net (code "232") (name "Net-(X15-Pad7)") (class "Default")
      (node (ref "X15") (pin "7") (pinfunction "7_7") (pintype "passive"))
    )
    (net (code "233") (name "Net-(X15-Pad8)") (class "Default")
      (node (ref "X15") (pin "8") (pinfunction "8_8") (pintype "passive"))
    )
    (net (code "234") (name "unconnected-(D9-io{slash}LOCK-Pad62)") (class "Default")
      (node (ref "D9") (pin "62") (pinfunction "io/LOCK_62") (pintype "passive"))
    )
    (net (code "235") (name "unconnected-(J21-Pad12)") (class "Default")
      (node (ref "J21") (pin "12") (pinfunction "12_12") (pintype "passive"))
    )
    (net (code "236") (name "unconnected-(X22-Pad1)") (class "Default")
      (node (ref "X22") (pin "1") (pinfunction "1_1") (pintype "passive"))
    )
    (net (code "237") (name "unconnected-(X23-Pad1)") (class "Default")
      (node (ref "X23") (pin "1") (pinfunction "1_1") (pintype "passive"))
    )
    (net (code "238") (name "unconnected-(X24-Pad1)") (class "Default")
      (node (ref "X24") (pin "1") (pinfunction "1_1") (pintype "passive"))
    )
  )
)
